# SCH_ESP32_AG_2025-02-10.net
KiCad netlist of a schematic drawn in EasyEDA
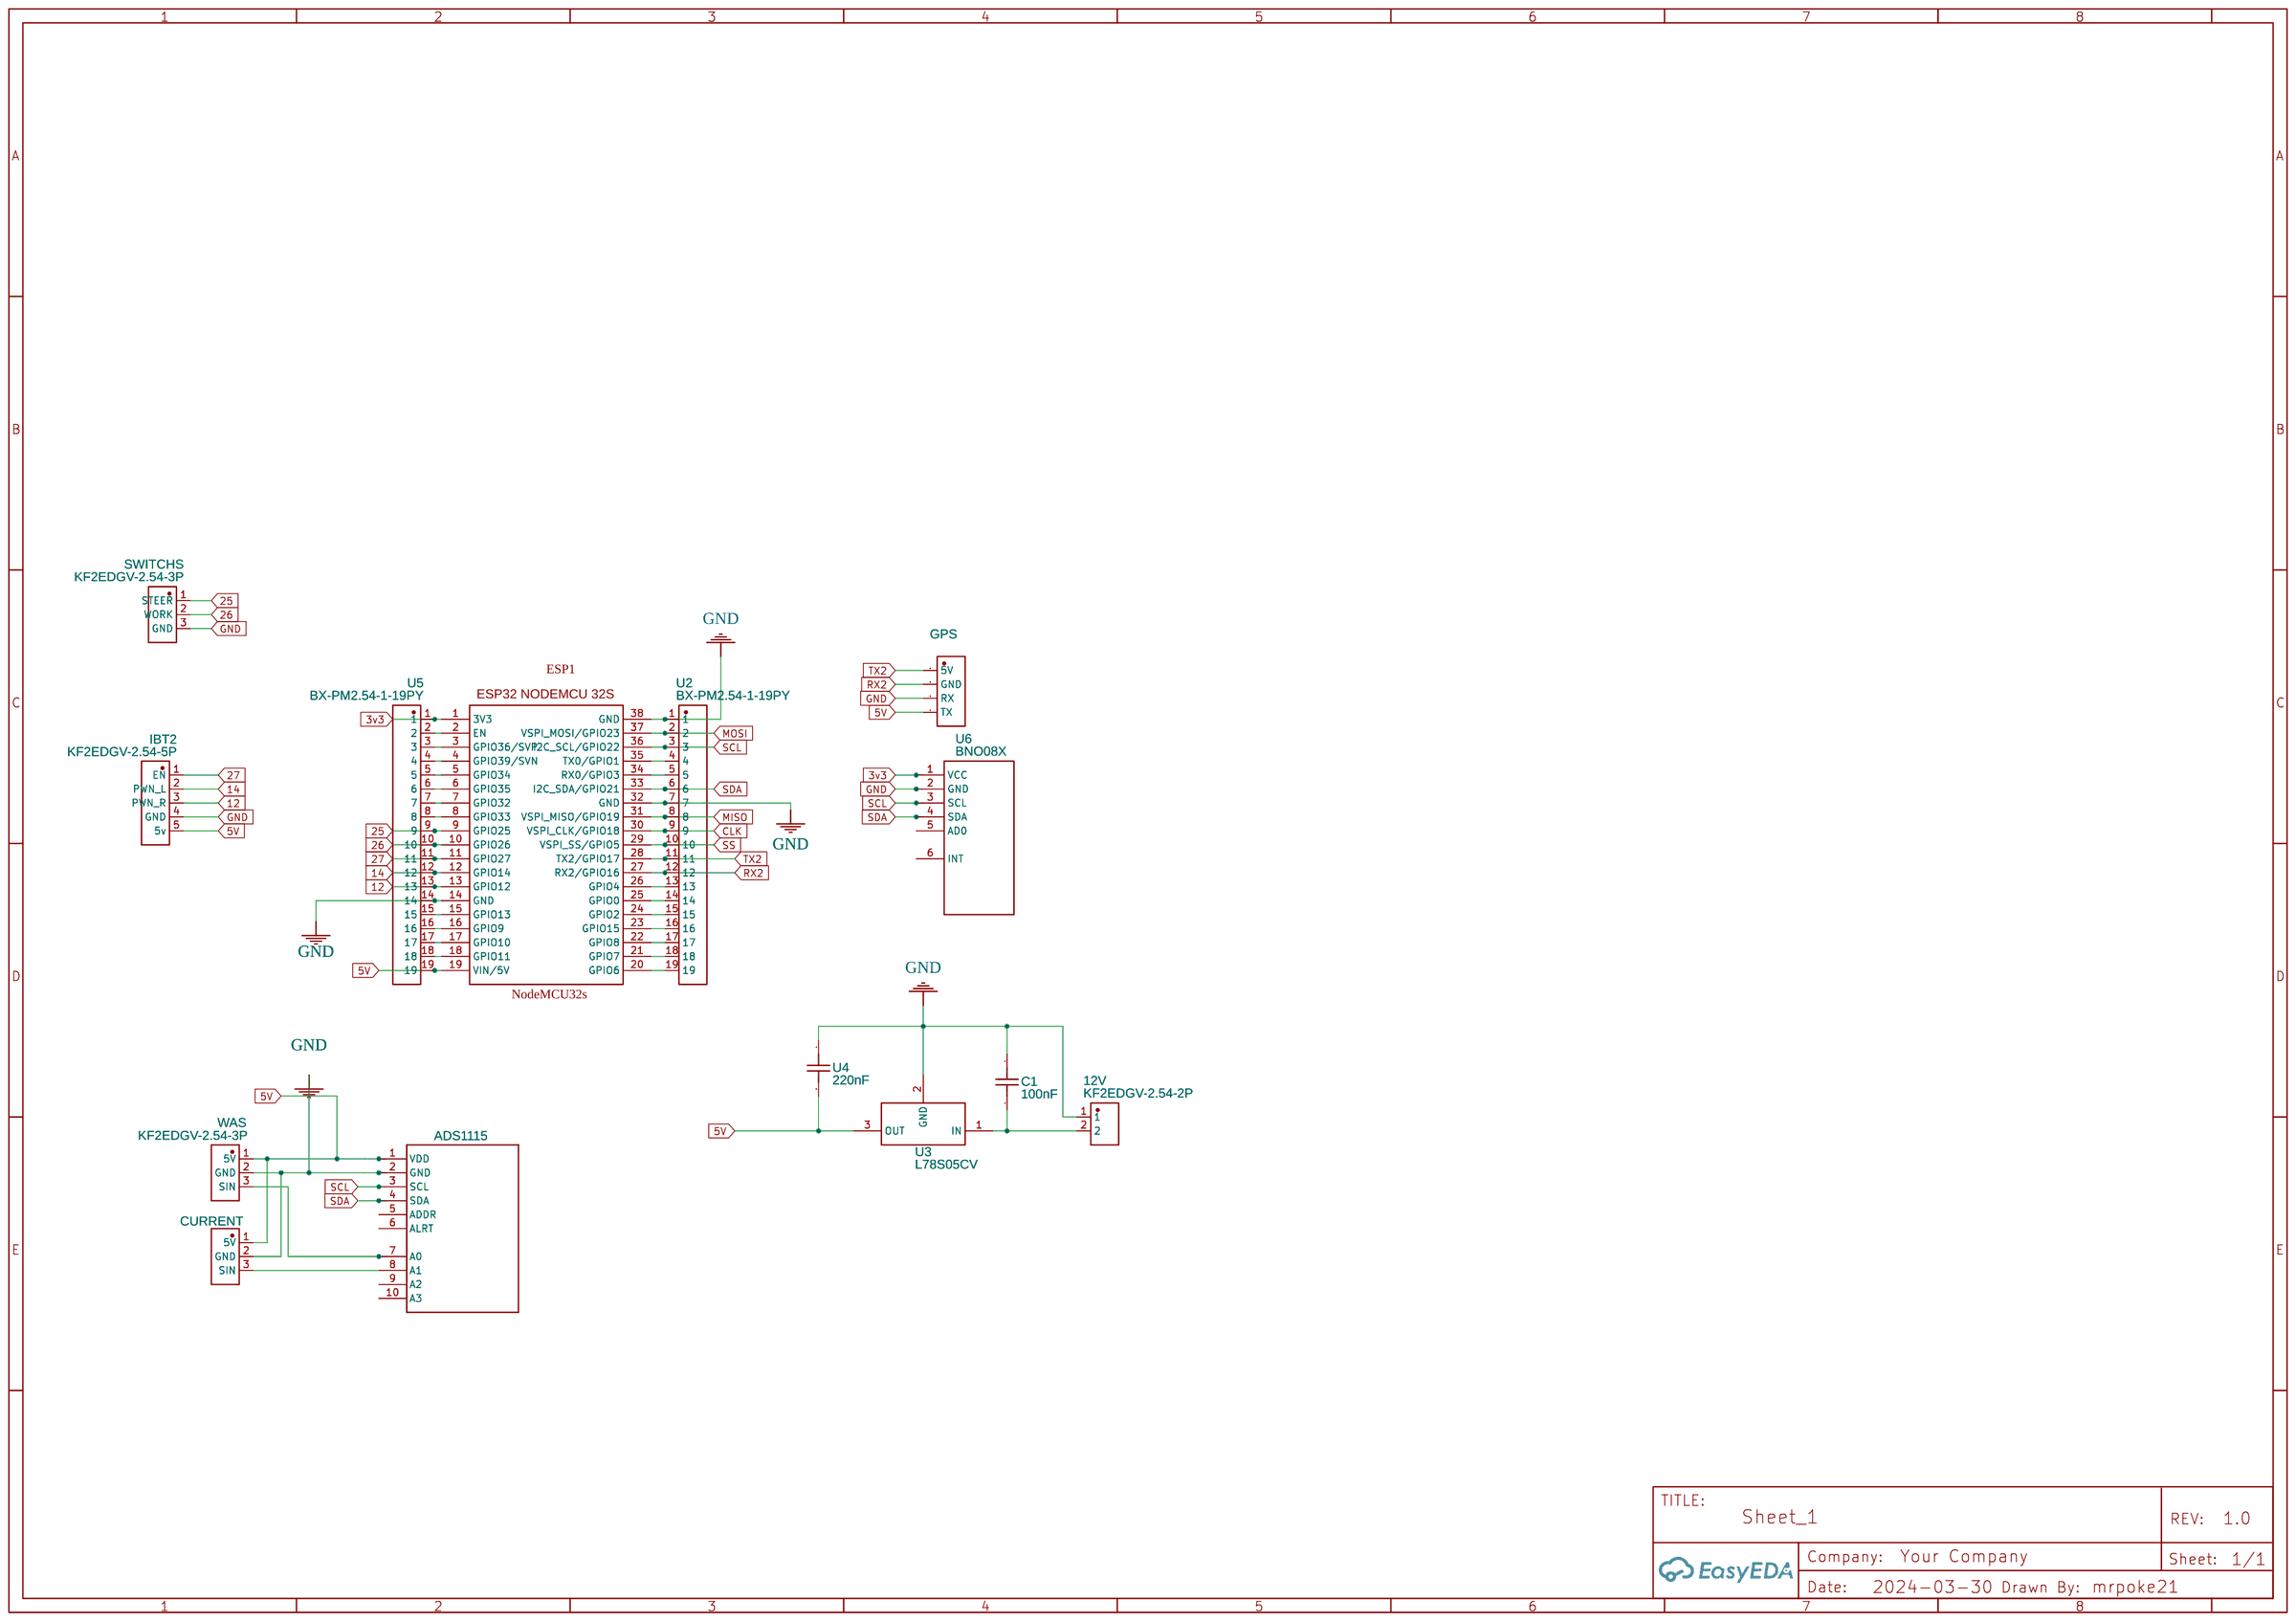
[diagram p0: schematic sheet]

(export (version "E")
  (design (tool "Eeschema 10.0.6"))
  (components
    (comp (ref "12V")
      (value "KF2EDGV-2.54-2P")
      (fields (field (name "Manufacturer") "KEFA(科发)"))
      (libsource (lib "") (part "KF2EDGV-2.54-2P"))
    )
    (comp (ref "ADS1115") (value "ADS1115") (libsource (lib "") (part "ADC-4CH-ADS1115 SIL")))
    (comp (ref "C1")
      (value "100nF")
      (fields
        (field (name "Manufacturer Part") "CC1H104ZA1ED3F5P1100")
        (field (name "Manufacturer") "Dersonic(德尔创)")
      )
      (libsource (lib "") (part "CC1H104ZA1ED3F5P1100"))
    )
    (comp (ref "CURRENT")
      (value "KF2EDGV-2.54-3P")
      (fields (field (name "Manufacturer") "KEFA(科发)"))
      (libsource (lib "") (part "KF2EDGV-2.54-3P_2"))
    )
    (comp (ref "GPS")
      (value "KF2EDGV-2.54-4P")
      (fields (field (name "Manufacturer") "KEFA(科发)"))
      (libsource (lib "") (part "KF2EDGV-2.54-4P"))
    )
    (comp (ref "IBT2")
      (value "KF2EDGV-2.54-5P")
      (fields (field (name "Manufacturer") "KEFA(科发)"))
      (libsource (lib "") (part "KF2EDGV-2.54-5P"))
    )
    (comp (ref "SWITCHS")
      (value "KF2EDGV-2.54-3P")
      (fields (field (name "Manufacturer") "KEFA(科发)"))
      (libsource (lib "") (part "KF2EDGV-2.54-3P"))
    )
    (comp (ref "U1") (value "NodeMCU ESP-32S") (libsource (lib "") (part "NodeMCU ESP-32S")))
    (comp (ref "U2")
      (value "BX-PM2.54-1-19PY")
      (fields (field (name "Manufacturer") "Bossie(博锡)"))
      (libsource (lib "") (part "BX-PM2.54-1-19PY_1"))
    )
    (comp (ref "U3")
      (value "L78S05CV")
      (fields (field (name "Manufacturer") "ST(意法半导体)"))
      (libsource (lib "") (part "L78S05CV"))
    )
    (comp (ref "U4")
      (value "220nF")
      (fields
        (field (name "Manufacturer Part") "CC1H224ZC1GD3F8A3100")
        (field (name "Manufacturer") "Dersonic(德尔创)")
      )
      (libsource (lib "") (part "CC1H224ZC1GD3F8A3100"))
    )
    (comp (ref "U5")
      (value "BX-PM2.54-1-19PY")
      (fields (field (name "Manufacturer") "Bossie(博锡)"))
      (libsource (lib "") (part "BX-PM2.54-1-19PY"))
    )
    (comp (ref "U6") (value "BNO08X") (libsource (lib "") (part "BNO08X")))
    (comp (ref "WAS")
      (value "KF2EDGV-2.54-3P")
      (fields (field (name "Manufacturer") "KEFA(科发)"))
      (libsource (lib "") (part "KF2EDGV-2.54-3P_1"))
    )
  )
  (nets
    (net (code "1") (name "3v3") (class "Default")
      (node (ref "U1") (pin "1") (pinfunction "3V3_1") (pintype "unspecified"))
      (node (ref "U5") (pin "1") (pinfunction "1_1") (pintype "unspecified"))
      (node (ref "U6") (pin "1") (pinfunction "VCC_1") (pintype "unspecified"))
    )
    (net (code "2") (name "5V") (class "Default")
      (node (ref "ADS1115") (pin "1") (pinfunction "VDD_1") (pintype "bidirectional"))
      (node (ref "CURRENT") (pin "1") (pinfunction "5V_1") (pintype "unspecified"))
      (node (ref "GPS") (pin "4") (pinfunction "TX_4") (pintype "output"))
      (node (ref "IBT2") (pin "5") (pinfunction "5v_5") (pintype "unspecified"))
      (node (ref "U1") (pin "19") (pinfunction "VIN/5V_19") (pintype "unspecified"))
      (node (ref "U3") (pin "3") (pinfunction "OUT_3") (pintype "passive"))
      (node (ref "U4") (pin "2") (pinfunction "2_2") (pintype "unspecified"))
      (node (ref "U5") (pin "19") (pinfunction "19_19") (pintype "unspecified"))
      (node (ref "WAS") (pin "1") (pinfunction "5V_1") (pintype "unspecified"))
    )
    (net (code "3") (name "12") (class "Default")
      (node (ref "IBT2") (pin "3") (pinfunction "PWN_R_3") (pintype "unspecified"))
      (node (ref "U1") (pin "13") (pinfunction "GPIO12_13") (pintype "unspecified"))
      (node (ref "U5") (pin "13") (pinfunction "13_13") (pintype "unspecified"))
    )
    (net (code "4") (name "14") (class "Default")
      (node (ref "IBT2") (pin "2") (pinfunction "PWN_L_2") (pintype "unspecified"))
      (node (ref "U1") (pin "12") (pinfunction "GPIO14_12") (pintype "unspecified"))
      (node (ref "U5") (pin "12") (pinfunction "12_12") (pintype "unspecified"))
    )
    (net (code "5") (name "25") (class "Default")
      (node (ref "SWITCHS") (pin "1") (pinfunction "STEER_1") (pintype "unspecified"))
      (node (ref "U1") (pin "9") (pinfunction "GPIO25_9") (pintype "unspecified"))
      (node (ref "U5") (pin "9") (pinfunction "9_9") (pintype "unspecified"))
    )
    (net (code "6") (name "26") (class "Default")
      (node (ref "SWITCHS") (pin "2") (pinfunction "WORK_2") (pintype "unspecified"))
      (node (ref "U1") (pin "10") (pinfunction "GPIO26_10") (pintype "unspecified"))
      (node (ref "U5") (pin "10") (pinfunction "10_10") (pintype "unspecified"))
    )
    (net (code "7") (name "27") (class "Default")
      (node (ref "IBT2") (pin "1") (pinfunction "EN_1") (pintype "unspecified"))
      (node (ref "U1") (pin "11") (pinfunction "GPIO27_11") (pintype "unspecified"))
      (node (ref "U5") (pin "11") (pinfunction "11_11") (pintype "unspecified"))
    )
    (net (code "8") (name "CLK") (class "Default")
      (node (ref "U1") (pin "30") (pinfunction "VSPI_CLK/GPIO18_30") (pintype "unspecified"))
      (node (ref "U2") (pin "9") (pinfunction "9_9") (pintype "unspecified"))
    )
    (net (code "9") (name "GND") (class "Default")
      (node (ref "12V") (pin "1") (pinfunction "1_1") (pintype "unspecified"))
      (node (ref "ADS1115") (pin "2") (pinfunction "GND_2") (pintype "bidirectional"))
      (node (ref "C1") (pin "1") (pinfunction "1_1") (pintype "unspecified"))
      (node (ref "CURRENT") (pin "2") (pinfunction "GND_2") (pintype "unspecified"))
      (node (ref "GPS") (pin "3") (pinfunction "RX_3") (pintype "input"))
      (node (ref "IBT2") (pin "4") (pinfunction "GND_4") (pintype "unspecified"))
      (node (ref "SWITCHS") (pin "3") (pinfunction "GND_3") (pintype "unspecified"))
      (node (ref "U1") (pin "14") (pinfunction "GND_14") (pintype "unspecified"))
      (node (ref "U1") (pin "32") (pinfunction "GND_32") (pintype "unspecified"))
      (node (ref "U1") (pin "38") (pinfunction "GND_38") (pintype "unspecified"))
      (node (ref "U2") (pin "1") (pinfunction "1_1") (pintype "unspecified"))
      (node (ref "U2") (pin "7") (pinfunction "7_7") (pintype "unspecified"))
      (node (ref "U3") (pin "2") (pinfunction "GND_2") (pintype "passive"))
      (node (ref "U4") (pin "1") (pinfunction "1_1") (pintype "unspecified"))
      (node (ref "U5") (pin "14") (pinfunction "14_14") (pintype "unspecified"))
      (node (ref "U6") (pin "2") (pinfunction "GND_2") (pintype "unspecified"))
      (node (ref "WAS") (pin "2") (pinfunction "GND_2") (pintype "unspecified"))
    )
    (net (code "10") (name "MISO") (class "Default")
      (node (ref "U1") (pin "31") (pinfunction "VSPI_MISO/GPIO19_31") (pintype "unspecified"))
      (node (ref "U2") (pin "8") (pinfunction "8_8") (pintype "unspecified"))
    )
    (net (code "11") (name "MOSI") (class "Default")
      (node (ref "U1") (pin "37") (pinfunction "VSPI_MOSI/GPIO23_37") (pintype "unspecified"))
      (node (ref "U2") (pin "2") (pinfunction "2_2") (pintype "unspecified"))
    )
    (net (code "12") (name "Net-(ADS1115-A0)") (class "Default")
      (node (ref "ADS1115") (pin "7") (pinfunction "A0_7") (pintype "bidirectional"))
      (node (ref "WAS") (pin "3") (pinfunction "SIN_3") (pintype "unspecified"))
    )
    (net (code "13") (name "Net-(ADS1115-A1)") (class "Default")
      (node (ref "ADS1115") (pin "8") (pinfunction "A1_8") (pintype "bidirectional"))
      (node (ref "CURRENT") (pin "3") (pinfunction "SIN_3") (pintype "unspecified"))
    )
    (net (code "14") (name "Net-(U1-EN)") (class "Default")
      (node (ref "U1") (pin "2") (pinfunction "EN_2") (pintype "unspecified"))
      (node (ref "U5") (pin "2") (pinfunction "2_2") (pintype "unspecified"))
    )
    (net (code "15") (name "Net-(U1-GPIO0)") (class "Default")
      (node (ref "U1") (pin "25") (pinfunction "GPIO0_25") (pintype "unspecified"))
      (node (ref "U2") (pin "14") (pinfunction "14_14") (pintype "unspecified"))
    )
    (net (code "16") (name "Net-(U1-GPIO2)") (class "Default")
      (node (ref "U1") (pin "24") (pinfunction "GPIO2_24") (pintype "unspecified"))
      (node (ref "U2") (pin "15") (pinfunction "15_15") (pintype "unspecified"))
    )
    (net (code "17") (name "Net-(U1-GPIO4)") (class "Default")
      (node (ref "U1") (pin "26") (pinfunction "GPIO4_26") (pintype "unspecified"))
      (node (ref "U2") (pin "13") (pinfunction "13_13") (pintype "unspecified"))
    )
    (net (code "18") (name "Net-(U1-GPIO6)") (class "Default")
      (node (ref "U1") (pin "20") (pinfunction "GPIO6_20") (pintype "unspecified"))
      (node (ref "U2") (pin "19") (pinfunction "19_19") (pintype "unspecified"))
    )
    (net (code "19") (name "Net-(U1-GPIO7)") (class "Default")
      (node (ref "U1") (pin "21") (pinfunction "GPIO7_21") (pintype "unspecified"))
      (node (ref "U2") (pin "18") (pinfunction "18_18") (pintype "unspecified"))
    )
    (net (code "20") (name "Net-(U1-GPIO8)") (class "Default")
      (node (ref "U1") (pin "22") (pinfunction "GPIO8_22") (pintype "unspecified"))
      (node (ref "U2") (pin "17") (pinfunction "17_17") (pintype "unspecified"))
    )
    (net (code "21") (name "Net-(U1-GPIO9)") (class "Default")
      (node (ref "U1") (pin "16") (pinfunction "GPIO9_16") (pintype "unspecified"))
      (node (ref "U5") (pin "16") (pinfunction "16_16") (pintype "unspecified"))
    )
    (net (code "22") (name "Net-(U1-GPIO10)") (class "Default")
      (node (ref "U1") (pin "17") (pinfunction "GPIO10_17") (pintype "unspecified"))
      (node (ref "U5") (pin "17") (pinfunction "17_17") (pintype "unspecified"))
    )
    (net (code "23") (name "Net-(U1-GPIO11)") (class "Default")
      (node (ref "U1") (pin "18") (pinfunction "GPIO11_18") (pintype "unspecified"))
      (node (ref "U5") (pin "18") (pinfunction "18_18") (pintype "unspecified"))
    )
    (net (code "24") (name "Net-(U1-GPIO13)") (class "Default")
      (node (ref "U1") (pin "15") (pinfunction "GPIO13_15") (pintype "unspecified"))
      (node (ref "U5") (pin "15") (pinfunction "15_15") (pintype "unspecified"))
    )
    (net (code "25") (name "Net-(U1-GPIO15)") (class "Default")
      (node (ref "U1") (pin "23") (pinfunction "GPIO15_23") (pintype "unspecified"))
      (node (ref "U2") (pin "16") (pinfunction "16_16") (pintype "unspecified"))
    )
    (net (code "26") (name "Net-(U1-GPIO32)") (class "Default")
      (node (ref "U1") (pin "7") (pinfunction "GPIO32_7") (pintype "unspecified"))
      (node (ref "U5") (pin "7") (pinfunction "7_7") (pintype "unspecified"))
    )
    (net (code "27") (name "Net-(U1-GPIO33)") (class "Default")
      (node (ref "U1") (pin "8") (pinfunction "GPIO33_8") (pintype "unspecified"))
      (node (ref "U5") (pin "8") (pinfunction "8_8") (pintype "unspecified"))
    )
    (net (code "28") (name "Net-(U1-GPIO34)") (class "Default")
      (node (ref "U1") (pin "5") (pinfunction "GPIO34_5") (pintype "unspecified"))
      (node (ref "U5") (pin "5") (pinfunction "5_5") (pintype "unspecified"))
    )
    (net (code "29") (name "Net-(U1-GPIO35)") (class "Default")
      (node (ref "U1") (pin "6") (pinfunction "GPIO35_6") (pintype "unspecified"))
      (node (ref "U5") (pin "6") (pinfunction "6_6") (pintype "unspecified"))
    )
    (net (code "30") (name "Net-(U1-GPIO36{slash}SVP)") (class "Default")
      (node (ref "U1") (pin "3") (pinfunction "GPIO36/SVP_3") (pintype "unspecified"))
      (node (ref "U5") (pin "3") (pinfunction "3_3") (pintype "unspecified"))
    )
    (net (code "31") (name "Net-(U1-GPIO39{slash}SVN)") (class "Default")
      (node (ref "U1") (pin "4") (pinfunction "GPIO39/SVN_4") (pintype "unspecified"))
      (node (ref "U5") (pin "4") (pinfunction "4_4") (pintype "unspecified"))
    )
    (net (code "32") (name "Net-(U1-RX0{slash}GPIO3)") (class "Default")
      (node (ref "U1") (pin "34") (pinfunction "RX0/GPIO3_34") (pintype "unspecified"))
      (node (ref "U2") (pin "5") (pinfunction "5_5") (pintype "unspecified"))
    )
    (net (code "33") (name "Net-(U1-TX0{slash}GPIO1)") (class "Default")
      (node (ref "U1") (pin "35") (pinfunction "TX0/GPIO1_35") (pintype "unspecified"))
      (node (ref "U2") (pin "4") (pinfunction "4_4") (pintype "unspecified"))
    )
    (net (code "34") (name "Net-(U3-IN)") (class "Default")
      (node (ref "12V") (pin "2") (pinfunction "2_2") (pintype "unspecified"))
      (node (ref "C1") (pin "2") (pinfunction "2_2") (pintype "unspecified"))
      (node (ref "U3") (pin "1") (pinfunction "IN_1") (pintype "passive"))
    )
    (net (code "35") (name "RX2") (class "Default")
      (node (ref "GPS") (pin "2") (pinfunction "GND_2") (pintype "passive"))
      (node (ref "U1") (pin "27") (pinfunction "RX2/GPIO16_27") (pintype "unspecified"))
      (node (ref "U2") (pin "12") (pinfunction "12_12") (pintype "unspecified"))
    )
    (net (code "36") (name "SCL") (class "Default")
      (node (ref "ADS1115") (pin "3") (pinfunction "SCL_3") (pintype "bidirectional"))
      (node (ref "U1") (pin "36") (pinfunction "I2C_SCL/GPIO22_36") (pintype "unspecified"))
      (node (ref "U2") (pin "3") (pinfunction "3_3") (pintype "unspecified"))
      (node (ref "U6") (pin "3") (pinfunction "SCL_3") (pintype "unspecified"))
    )
    (net (code "37") (name "SDA") (class "Default")
      (node (ref "ADS1115") (pin "4") (pinfunction "SDA_4") (pintype "bidirectional"))
      (node (ref "U1") (pin "33") (pinfunction "I2C_SDA/GPIO21_33") (pintype "unspecified"))
      (node (ref "U2") (pin "6") (pinfunction "6_6") (pintype "unspecified"))
      (node (ref "U6") (pin "4") (pinfunction "SDA_4") (pintype "unspecified"))
    )
    (net (code "38") (name "SS") (class "Default")
      (node (ref "U1") (pin "29") (pinfunction "VSPI_SS/GPIO5_29") (pintype "unspecified"))
      (node (ref "U2") (pin "10") (pinfunction "10_10") (pintype "unspecified"))
    )
    (net (code "39") (name "TX2") (class "Default")
      (node (ref "GPS") (pin "1") (pinfunction "5V_1") (pintype "passive"))
      (node (ref "U1") (pin "28") (pinfunction "TX2/GPIO17_28") (pintype "unspecified"))
      (node (ref "U2") (pin "11") (pinfunction "11_11") (pintype "unspecified"))
    )
    (net (code "40") (name "unconnected-(ADS1115-A2-Pad9)") (class "Default")
      (node (ref "ADS1115") (pin "9") (pinfunction "A2_9") (pintype "bidirectional"))
    )
    (net (code "41") (name "unconnected-(ADS1115-A3-Pad10)") (class "Default")
      (node (ref "ADS1115") (pin "10") (pinfunction "A3_10") (pintype "bidirectional"))
    )
    (net (code "42") (name "unconnected-(ADS1115-ADDR-Pad5)") (class "Default")
      (node (ref "ADS1115") (pin "5") (pinfunction "ADDR_5") (pintype "bidirectional"))
    )
    (net (code "43") (name "unconnected-(ADS1115-ALRT-Pad6)") (class "Default")
      (node (ref "ADS1115") (pin "6") (pinfunction "ALRT_6") (pintype "bidirectional"))
    )
    (net (code "44") (name "unconnected-(U6-AD0-Pad5)") (class "Default")
      (node (ref "U6") (pin "5") (pinfunction "AD0_5") (pintype "unspecified"))
    )
    (net (code "45") (name "unconnected-(U6-INT-Pad6)") (class "Default")
      (node (ref "U6") (pin "6") (pinfunction "INT_6") (pintype "unspecified"))
    )
  )
)
